# Main.net
KiCad netlist of a schematic drawn in Altium Designer
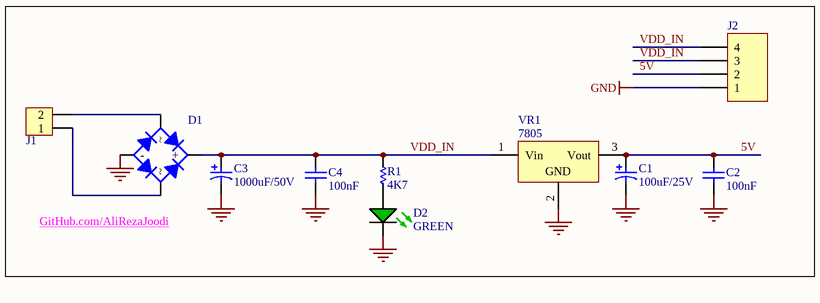
[diagram p0: Main.SchDoc]

(export (version "E")
  (design (tool "Eeschema 10.0.6"))
  (components
    (comp (ref "C1")
      (value "100uF/25V")
      (footprint "C_THD_EL_(P3.4-D8-H7)")
      (description "Capacitor, Electrolytic")
      (libsource (lib "Passive") (part "Capacitor_Electrolytic"))
    )
    (comp (ref "C2")
      (value "100nF")
      (footprint "C_THD_CER_(P2.54-D3.5-T1.5)")
      (description "Capacitor, Ceramic Multilayer")
      (libsource (lib "Passive") (part "Capacitor_Ceramic"))
    )
    (comp (ref "C3")
      (value "1000uF/50V")
      (footprint "C_THD_EL_(P3.4-D8-H7)")
      (description "Capacitor, Electrolytic")
      (libsource (lib "Passive") (part "Capacitor_Electrolytic"))
    )
    (comp (ref "C4")
      (value "100nF")
      (footprint "C_THD_CER_(P2.54-D3.5-T1.5)")
      (description "Capacitor, Ceramic Multilayer")
      (libsource (lib "Passive") (part "Capacitor_Ceramic"))
    )
    (comp (ref "D1")
      (value "Bridge1")
      (footprint "BRIDGE-1")
      (description "Full Wave Diode Bridge")
      (fields (field (name "MANUFACTURER") "Generic Components") (field (name "PUBLISHER") "Altium Limited"))
      (libsource (lib "Miscellaneous Devices") (part "Bridge1"))
    )
    (comp (ref "D2")
      (value "GREEN")
      (footprint "LED_THD_5MM_GREEN")
      (description "LED, Green")
      (fields (field (name "MANUFACTURER") "Generic Components") (field (name "PUBLISHER") "Altium Limited"))
      (libsource (lib "Display") (part "LED_GREEN"))
    )
    (comp (ref "J1")
      (value "2PIN")
      (footprint "Connector_Phoenix_2PIN_MSTB")
      (description "Connector, Header, 2Pin")
      (libsource (lib "Connector") (part "Connector_Header_2Pin"))
    )
    (comp (ref "J2")
      (value "4Pin")
      (footprint "HDR1X4")
      (description "Header, 4-Pin")
      (fields (field (name "MANUFACTURER") "Generic Components") (field (name "PUBLISHER") "Altium Limited"))
      (libsource (lib "Miscellaneous Connectors") (part "Header 4"))
    )
    (comp (ref "R1")
      (value "4K7")
      (footprint "R_THD_AXIAL0.4(1/4W)")
      (description "Resistor")
      (libsource (lib "Passive") (part "Resistor"))
    )
    (comp (ref "VR1")
      (value "7805")
      (footprint "TO220_3PIN_V")
      (description "Voltage Regulator, Linear, Fixed, 5v, 1.5A")
      (libsource (lib "Other_Myself") (part "Volt Reg"))
    )
  )
  (nets
    (net (code "1") (name "/5V") (class "Default")
      (node (ref "C1") (pin "1") (pinfunction "1_1") (pintype "passive"))
      (node (ref "C2") (pin "1") (pinfunction "1_1") (pintype "passive"))
      (node (ref "J2") (pin "2") (pinfunction "2_2") (pintype "passive"))
      (node (ref "VR1") (pin "3") (pinfunction "Vout_3") (pintype "passive"))
    )
    (net (code "2") (name "/VDD_IN") (class "Default")
      (node (ref "C3") (pin "1") (pinfunction "1_1") (pintype "passive"))
      (node (ref "C4") (pin "1") (pinfunction "1_1") (pintype "passive"))
      (node (ref "D1") (pin "3") (pinfunction "+_3") (pintype "passive"))
      (node (ref "J2") (pin "3") (pinfunction "3_3") (pintype "passive"))
      (node (ref "J2") (pin "4") (pinfunction "4_4") (pintype "passive"))
      (node (ref "R1") (pin "2") (pinfunction "2_2") (pintype "passive"))
      (node (ref "VR1") (pin "1") (pinfunction "Vin_1") (pintype "passive"))
    )
    (net (code "3") (name "GND") (class "Default")
      (node (ref "C1") (pin "2") (pinfunction "2_2") (pintype "passive"))
      (node (ref "C2") (pin "2") (pinfunction "2_2") (pintype "passive"))
      (node (ref "C3") (pin "2") (pinfunction "2_2") (pintype "passive"))
      (node (ref "C4") (pin "2") (pinfunction "2_2") (pintype "passive"))
      (node (ref "D1") (pin "1") (pinfunction "-_1") (pintype "passive"))
      (node (ref "D2") (pin "2") (pinfunction "K_2") (pintype "passive"))
      (node (ref "J2") (pin "1") (pinfunction "1_1") (pintype "passive"))
      (node (ref "VR1") (pin "2") (pinfunction "GND_2") (pintype "passive"))
    )
    (net (code "4") (name "Net-(D1-~-Pad2)") (class "Default")
      (node (ref "D1") (pin "2") (pinfunction "~_2") (pintype "passive"))
      (node (ref "J1") (pin "2") (pinfunction "2_2") (pintype "passive"))
    )
    (net (code "5") (name "Net-(D1-~-Pad4)") (class "Default")
      (node (ref "D1") (pin "4") (pinfunction "~_4") (pintype "passive"))
      (node (ref "J1") (pin "1") (pinfunction "1_1") (pintype "passive"))
    )
    (net (code "6") (name "Net-(D2-A)") (class "Default")
      (node (ref "D2") (pin "1") (pinfunction "A_1") (pintype "passive"))
      (node (ref "R1") (pin "1") (pinfunction "1_1") (pintype "passive"))
    )
  )
)
